# Main.net
KiCad netlist of a schematic drawn in Altium Designer
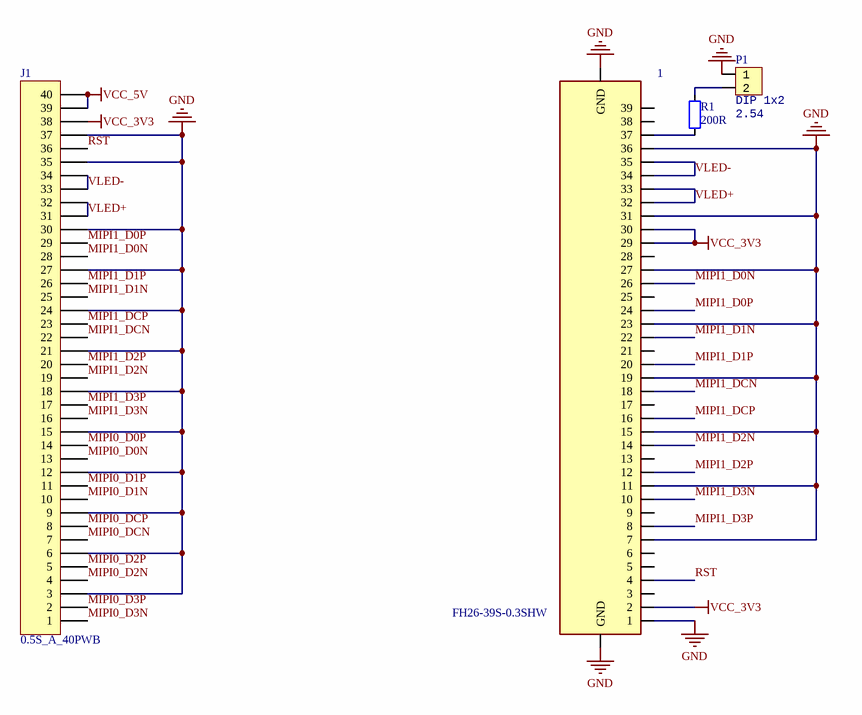
[diagram p0: Main.SchDoc]

(export (version "E")
  (design (tool "Eeschema 10.0.6"))
  (components
    (comp (ref "1")
      (value "FH26-39S-0.3SHW")
      (footprint "mLib:FH26-39S-0.3SHW")
      (description "39 Position FPC Connector Contacts, Bottom 0.012 _0.30mm_ Surface Mount, Right Angle")
      (fields (field (name "MF") "Hirose"))
      (libsource (lib "mLib") (part "FH26-39S-0.3SHW"))
    )
    (comp (ref "J1")
      (value "0.5S_A_40PWB")
      (footprint "FFC_0.5_40")
      (description "Header, 40-Pin")
      (fields (field (name "PUBLISHER") "Altium Limited"))
      (libsource (lib "MyPcbLib") (part "FPC40-0.5mm"))
    )
    (comp (ref "P1")
      (value "2.54")
      (footprint "HDR1X2_2.54_180")
      (description "Header")
      (fields (field (name "TYPE") "DIP 1x2") (field (name "Comment") "DIP 1x2"))
      (libsource (lib "KitSprout") (part "HDR1x2_2.54"))
    )
    (comp (ref "R1")
      (value "200R")
      (footprint "RES_0402")
      (description "Resistor")
      (libsource (lib "MyPcbLib") (part "电阻-0402"))
    )
  )
  (nets
    (net (code "1") (name "/MIPI0_D0N") (class "Default")
      (node (ref "J1") (pin "13") (pinfunction "13_13") (pintype "passive"))
    )
    (net (code "2") (name "/MIPI0_D0P") (class "Default")
      (node (ref "J1") (pin "14") (pinfunction "14_14") (pintype "passive"))
    )
    (net (code "3") (name "/MIPI0_D1N") (class "Default")
      (node (ref "J1") (pin "10") (pinfunction "10_10") (pintype "passive"))
    )
    (net (code "4") (name "/MIPI0_D1P") (class "Default")
      (node (ref "J1") (pin "11") (pinfunction "11_11") (pintype "passive"))
    )
    (net (code "5") (name "/MIPI0_D2N") (class "Default")
      (node (ref "J1") (pin "4") (pinfunction "4_4") (pintype "passive"))
    )
    (net (code "6") (name "/MIPI0_D2P") (class "Default")
      (node (ref "J1") (pin "5") (pinfunction "5_5") (pintype "passive"))
    )
    (net (code "7") (name "/MIPI0_D3N") (class "Default")
      (node (ref "J1") (pin "1") (pinfunction "1_1") (pintype "passive"))
    )
    (net (code "8") (name "/MIPI0_D3P") (class "Default")
      (node (ref "J1") (pin "2") (pinfunction "2_2") (pintype "passive"))
    )
    (net (code "9") (name "/MIPI0_DCN") (class "Default")
      (node (ref "J1") (pin "7") (pinfunction "7_7") (pintype "passive"))
    )
    (net (code "10") (name "/MIPI0_DCP") (class "Default")
      (node (ref "J1") (pin "8") (pinfunction "8_8") (pintype "passive"))
    )
    (net (code "11") (name "/MIPI1_D0N") (class "Default")
      (node (ref "1") (pin "26") (pinfunction "26_26") (pintype "bidirectional"))
      (node (ref "J1") (pin "28") (pinfunction "28_28") (pintype "passive"))
    )
    (net (code "12") (name "/MIPI1_D0P") (class "Default")
      (node (ref "1") (pin "24") (pinfunction "24_24") (pintype "bidirectional"))
      (node (ref "J1") (pin "29") (pinfunction "29_29") (pintype "passive"))
    )
    (net (code "13") (name "/MIPI1_D1N") (class "Default")
      (node (ref "1") (pin "22") (pinfunction "22_22") (pintype "bidirectional"))
      (node (ref "J1") (pin "25") (pinfunction "25_25") (pintype "passive"))
    )
    (net (code "14") (name "/MIPI1_D1P") (class "Default")
      (node (ref "1") (pin "20") (pinfunction "20_20") (pintype "bidirectional"))
      (node (ref "J1") (pin "26") (pinfunction "26_26") (pintype "passive"))
    )
    (net (code "15") (name "/MIPI1_D2N") (class "Default")
      (node (ref "1") (pin "14") (pinfunction "14_14") (pintype "bidirectional"))
      (node (ref "J1") (pin "19") (pinfunction "19_19") (pintype "passive"))
    )
    (net (code "16") (name "/MIPI1_D2P") (class "Default")
      (node (ref "1") (pin "12") (pinfunction "12_12") (pintype "bidirectional"))
      (node (ref "J1") (pin "20") (pinfunction "20_20") (pintype "passive"))
    )
    (net (code "17") (name "/MIPI1_D3N") (class "Default")
      (node (ref "1") (pin "10") (pinfunction "10_10") (pintype "bidirectional"))
      (node (ref "J1") (pin "16") (pinfunction "16_16") (pintype "passive"))
    )
    (net (code "18") (name "/MIPI1_D3P") (class "Default")
      (node (ref "1") (pin "8") (pinfunction "8_8") (pintype "bidirectional"))
      (node (ref "J1") (pin "17") (pinfunction "17_17") (pintype "passive"))
    )
    (net (code "19") (name "/MIPI1_DCN") (class "Default")
      (node (ref "1") (pin "18") (pinfunction "18_18") (pintype "bidirectional"))
      (node (ref "J1") (pin "22") (pinfunction "22_22") (pintype "passive"))
    )
    (net (code "20") (name "/MIPI1_DCP") (class "Default")
      (node (ref "1") (pin "16") (pinfunction "16_16") (pintype "bidirectional"))
      (node (ref "J1") (pin "23") (pinfunction "23_23") (pintype "passive"))
    )
    (net (code "21") (name "/RST") (class "Default")
      (node (ref "1") (pin "4") (pinfunction "4_4") (pintype "bidirectional"))
      (node (ref "J1") (pin "36") (pinfunction "36_36") (pintype "passive"))
    )
    (net (code "22") (name "/VLED+") (class "Default")
      (node (ref "1") (pin "32") (pinfunction "32_32") (pintype "bidirectional"))
      (node (ref "1") (pin "33") (pinfunction "33_33") (pintype "bidirectional"))
      (node (ref "J1") (pin "31") (pinfunction "31_31") (pintype "passive"))
      (node (ref "J1") (pin "32") (pinfunction "32_32") (pintype "passive"))
    )
    (net (code "23") (name "/VLED-") (class "Default")
      (node (ref "1") (pin "34") (pinfunction "34_34") (pintype "bidirectional"))
      (node (ref "1") (pin "35") (pinfunction "35_35") (pintype "bidirectional"))
      (node (ref "J1") (pin "33") (pinfunction "33_33") (pintype "passive"))
      (node (ref "J1") (pin "34") (pinfunction "34_34") (pintype "passive"))
    )
    (net (code "24") (name "GND") (class "Default")
      (node (ref "1") (pin "1") (pinfunction "1_1") (pintype "bidirectional"))
      (node (ref "1") (pin "11") (pinfunction "11_11") (pintype "bidirectional"))
      (node (ref "1") (pin "15") (pinfunction "15_15") (pintype "bidirectional"))
      (node (ref "1") (pin "19") (pinfunction "19_19") (pintype "bidirectional"))
      (node (ref "1") (pin "23") (pinfunction "23_23") (pintype "bidirectional"))
      (node (ref "1") (pin "27") (pinfunction "27_27") (pintype "bidirectional"))
      (node (ref "1") (pin "31") (pinfunction "31_31") (pintype "bidirectional"))
      (node (ref "1") (pin "36") (pinfunction "36_36") (pintype "bidirectional"))
      (node (ref "1") (pin "7") (pinfunction "7_7") (pintype "bidirectional"))
      (node (ref "1") (pin "GND1") (pinfunction "GND_GND1") (pintype "power_in"))
      (node (ref "1") (pin "GND2") (pinfunction "GND_GND2") (pintype "power_in"))
      (node (ref "J1") (pin "12") (pinfunction "12_12") (pintype "passive"))
      (node (ref "J1") (pin "15") (pinfunction "15_15") (pintype "passive"))
      (node (ref "J1") (pin "18") (pinfunction "18_18") (pintype "passive"))
      (node (ref "J1") (pin "21") (pinfunction "21_21") (pintype "passive"))
      (node (ref "J1") (pin "24") (pinfunction "24_24") (pintype "passive"))
      (node (ref "J1") (pin "27") (pinfunction "27_27") (pintype "passive"))
      (node (ref "J1") (pin "3") (pinfunction "3_3") (pintype "passive"))
      (node (ref "J1") (pin "30") (pinfunction "30_30") (pintype "passive"))
      (node (ref "J1") (pin "35") (pinfunction "35_35") (pintype "passive"))
      (node (ref "J1") (pin "37") (pinfunction "37_37") (pintype "passive"))
      (node (ref "J1") (pin "6") (pinfunction "6_6") (pintype "passive"))
      (node (ref "J1") (pin "9") (pinfunction "9_9") (pintype "passive"))
      (node (ref "P1") (pin "1") (pinfunction "1_1") (pintype "passive"))
    )
    (net (code "25") (name "Net-(1-Pad37)") (class "Default")
      (node (ref "1") (pin "37") (pinfunction "37_37") (pintype "bidirectional"))
      (node (ref "R1") (pin "1") (pinfunction "1_1") (pintype "passive"))
    )
    (net (code "26") (name "Net-(P1-Pad2)") (class "Default")
      (node (ref "P1") (pin "2") (pinfunction "2_2") (pintype "passive"))
      (node (ref "R1") (pin "2") (pinfunction "2_2") (pintype "passive"))
    )
    (net (code "27") (name "VCC_3V3") (class "Default")
      (node (ref "1") (pin "2") (pinfunction "2_2") (pintype "bidirectional"))
      (node (ref "1") (pin "29") (pinfunction "29_29") (pintype "bidirectional"))
      (node (ref "1") (pin "30") (pinfunction "30_30") (pintype "bidirectional"))
      (node (ref "J1") (pin "38") (pinfunction "38_38") (pintype "passive"))
    )
    (net (code "28") (name "VCC_5V") (class "Default")
      (node (ref "J1") (pin "39") (pinfunction "39_39") (pintype "passive"))
      (node (ref "J1") (pin "40") (pinfunction "40_40") (pintype "passive"))
    )
    (net (code "29") (name "unconnected-(1-Pad3)") (class "Default")
      (node (ref "1") (pin "3") (pinfunction "3_3") (pintype "bidirectional"))
    )
    (net (code "30") (name "unconnected-(1-Pad5)") (class "Default")
      (node (ref "1") (pin "5") (pinfunction "5_5") (pintype "bidirectional"))
    )
    (net (code "31") (name "unconnected-(1-Pad6)") (class "Default")
      (node (ref "1") (pin "6") (pinfunction "6_6") (pintype "bidirectional"))
    )
    (net (code "32") (name "unconnected-(1-Pad9)") (class "Default")
      (node (ref "1") (pin "9") (pinfunction "9_9") (pintype "bidirectional"))
    )
    (net (code "33") (name "unconnected-(1-Pad13)") (class "Default")
      (node (ref "1") (pin "13") (pinfunction "13_13") (pintype "bidirectional"))
    )
    (net (code "34") (name "unconnected-(1-Pad17)") (class "Default")
      (node (ref "1") (pin "17") (pinfunction "17_17") (pintype "bidirectional"))
    )
    (net (code "35") (name "unconnected-(1-Pad21)") (class "Default")
      (node (ref "1") (pin "21") (pinfunction "21_21") (pintype "bidirectional"))
    )
    (net (code "36") (name "unconnected-(1-Pad25)") (class "Default")
      (node (ref "1") (pin "25") (pinfunction "25_25") (pintype "bidirectional"))
    )
    (net (code "37") (name "unconnected-(1-Pad28)") (class "Default")
      (node (ref "1") (pin "28") (pinfunction "28_28") (pintype "bidirectional"))
    )
    (net (code "38") (name "unconnected-(1-Pad38)") (class "Default")
      (node (ref "1") (pin "38") (pinfunction "38_38") (pintype "bidirectional"))
    )
    (net (code "39") (name "unconnected-(1-Pad39)") (class "Default")
      (node (ref "1") (pin "39") (pinfunction "39_39") (pintype "bidirectional"))
    )
  )
)
